# PCB-PWR-CON.net
KiCad netlist of a schematic drawn in EAGLE
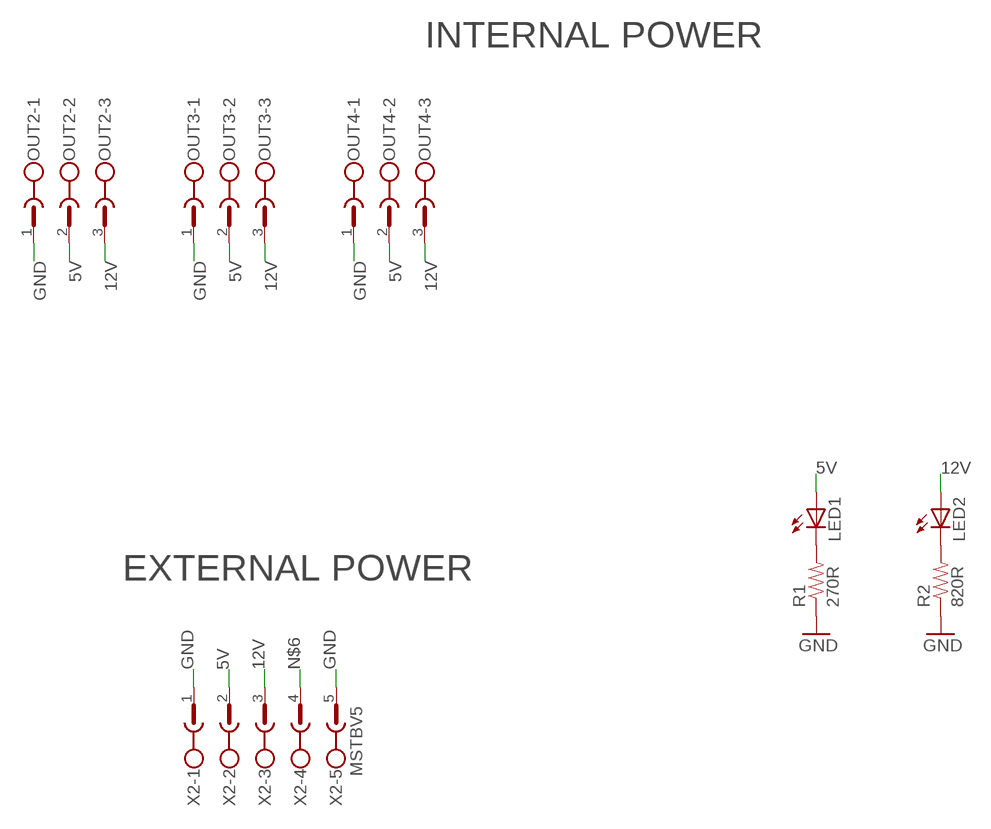
[diagram p0: schematic, sheet 1]

(export (version "E")
  (design (tool "Eeschema 10.0.6"))
  (components
    (comp (ref "LED1")
      (value "LED3MM")
      (footprint "eagle-import:LED3MM")
      (libsource (lib "eagle-import") (part "LED3MM"))
    )
    (comp (ref "LED2")
      (value "LED3MM")
      (footprint "eagle-import:LED3MM")
      (libsource (lib "eagle-import") (part "LED3MM"))
    )
    (comp (ref "OUT2")
      (value "CON1")
      (footprint "eagle-import:MSTBV3")
      (fields (field (name "MPN") "MSTBV 2,5/3-GF-5.08"))
      (libsource (lib "eagle-import") (part "MSTBV3"))
    )
    (comp (ref "OUT3")
      (value "CON1")
      (footprint "eagle-import:MSTBV3")
      (fields (field (name "MPN") "MSTBV 2,5/3-GF-5.08"))
      (libsource (lib "eagle-import") (part "MSTBV3"))
    )
    (comp (ref "OUT4")
      (value "CON1")
      (footprint "eagle-import:MSTBV3")
      (fields (field (name "MPN") "MSTBV 2,5/3-GF-5.08"))
      (libsource (lib "eagle-import") (part "MSTBV3"))
    )
    (comp (ref "R1")
      (value "270R")
      (footprint "eagle-import:0603-RES")
      (libsource (lib "eagle-import") (part "RESISTOR0603-RES"))
    )
    (comp (ref "R2")
      (value "820R")
      (footprint "eagle-import:0603-RES")
      (libsource (lib "eagle-import") (part "RESISTOR0603-RES"))
    )
    (comp (ref "X2")
      (value "MSTBV5")
      (footprint "eagle-import:MSTBV5")
      (fields (field (name "MPN") "MSTBV 2,5/5-GF-5.08"))
      (libsource (lib "eagle-import") (part "MSTBV5"))
    )
  )
  (nets
    (net (code "1") (name "/5V") (class "Default")
      (node (ref "LED1") (pin "A") (pinfunction "A_A") (pintype "passive"))
      (node (ref "OUT2") (pin "2") (pinfunction "1_2") (pintype "passive"))
      (node (ref "OUT3") (pin "2") (pinfunction "1_2") (pintype "passive"))
      (node (ref "OUT4") (pin "2") (pinfunction "1_2") (pintype "passive"))
      (node (ref "X2") (pin "2") (pinfunction "1_2") (pintype "passive"))
    )
    (net (code "2") (name "/12V") (class "Default")
      (node (ref "LED2") (pin "A") (pinfunction "A_A") (pintype "passive"))
      (node (ref "OUT2") (pin "3") (pinfunction "1_3") (pintype "passive"))
      (node (ref "OUT3") (pin "3") (pinfunction "1_3") (pintype "passive"))
      (node (ref "OUT4") (pin "3") (pinfunction "1_3") (pintype "passive"))
      (node (ref "X2") (pin "3") (pinfunction "1_3") (pintype "passive"))
    )
    (net (code "3") (name "/N$6") (class "Default")
      (node (ref "X2") (pin "4") (pinfunction "1_4") (pintype "passive"))
    )
    (net (code "4") (name "GND") (class "Default")
      (node (ref "OUT2") (pin "1") (pinfunction "1_1") (pintype "passive"))
      (node (ref "OUT3") (pin "1") (pinfunction "1_1") (pintype "passive"))
      (node (ref "OUT4") (pin "1") (pinfunction "1_1") (pintype "passive"))
      (node (ref "R1") (pin "1") (pinfunction "1_1") (pintype "passive"))
      (node (ref "R2") (pin "1") (pinfunction "1_1") (pintype "passive"))
      (node (ref "X2") (pin "1") (pinfunction "1_1") (pintype "passive"))
      (node (ref "X2") (pin "5") (pinfunction "1_5") (pintype "passive"))
    )
    (net (code "5") (name "Net-(LED1-C)") (class "Default")
      (node (ref "LED1") (pin "K") (pinfunction "C_K") (pintype "passive"))
      (node (ref "R1") (pin "2") (pinfunction "2_2") (pintype "passive"))
    )
    (net (code "6") (name "Net-(LED2-C)") (class "Default")
      (node (ref "LED2") (pin "K") (pinfunction "C_K") (pintype "passive"))
      (node (ref "R2") (pin "2") (pinfunction "2_2") (pintype "passive"))
    )
  )
)
